# PowerControl.net
KiCad netlist of a schematic drawn in Altium Designer
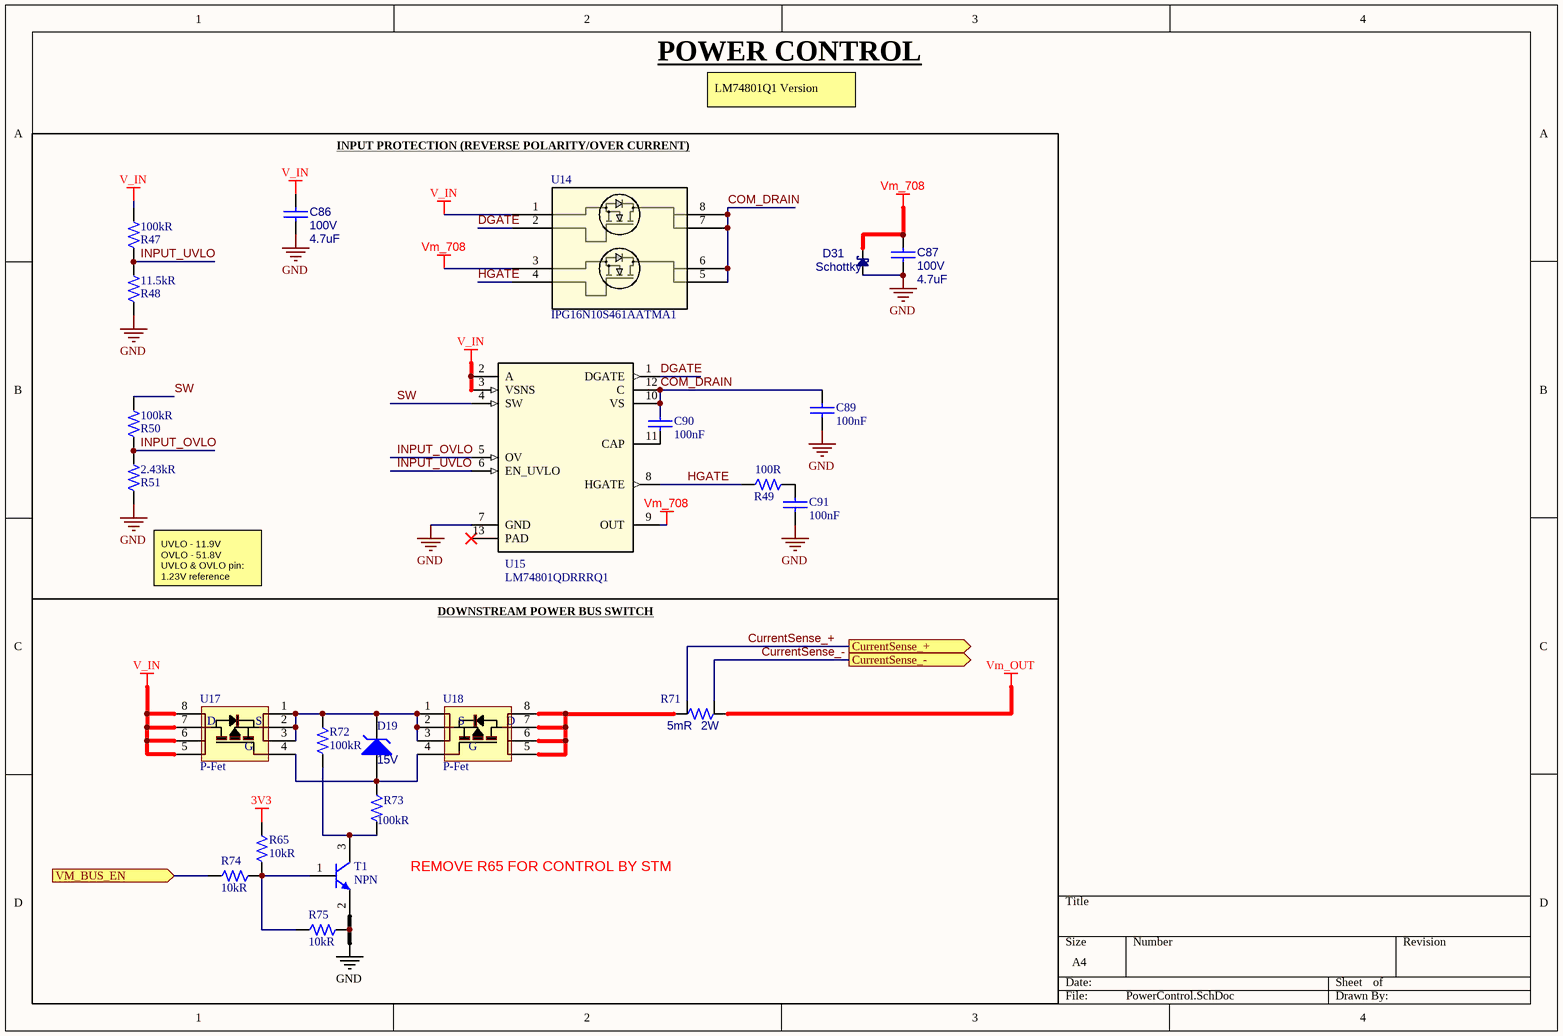
[diagram p0: PowerControl.SchDoc]

(export (version "E")
  (design (tool "Eeschema 10.0.6"))
  (components
    (comp (ref "C86")
      (value "4.7uF")
      (footprint "CAP1210")
      (description "Cap Ceramic 4.7uF 100V X7S 10% Pad SMD 1210 Soft Termination 125°C Automotive T/R")
      (fields
        (field (name "TOLERANCE") "10%")
        (field (name "VOLTAGE") "100V")
        (field (name "Comment") "Capacitor")
      )
      (libsource (lib "BPL-ShematicLibrary") (part "Capacitor"))
    )
    (comp (ref "C87")
      (value "4.7uF")
      (footprint "CAP1210")
      (description "Cap Ceramic 4.7uF 100V X7S 10% Pad SMD 1210 Soft Termination 125°C Automotive T/R")
      (fields
        (field (name "TOLERANCE") "10%")
        (field (name "VOLTAGE") "100V")
        (field (name "Comment") "Capacitor")
      )
      (libsource (lib "BPL-ShematicLibrary") (part "Capacitor"))
    )
    (comp (ref "C89")
      (value "Capacitor")
      (footprint "CAP0402")
      (description "Cap Ceramic 0.1uF 35V X7R 20% SMD 0402 125°C Punched Paper T/R")
      (fields (field (name "CAPACITANCE") "100nF"))
      (libsource (lib "BPL-ShematicLibrary") (part "Capacitor"))
    )
    (comp (ref "C90")
      (value "Capacitor")
      (footprint "CAP0402")
      (description "Cap Ceramic 0.1uF 35V X7R 20% SMD 0402 125°C Punched Paper T/R")
      (fields (field (name "CAPACITANCE") "100nF"))
      (libsource (lib "BPL-ShematicLibrary") (part "Capacitor"))
    )
    (comp (ref "C91")
      (value "Capacitor")
      (footprint "CAP0402")
      (description "Cap Ceramic 0.1uF 35V X7R 20% SMD 0402 125°C Punched Paper T/R")
      (fields (field (name "CAPACITANCE") "100nF"))
      (libsource (lib "BPL-ShematicLibrary") (part "Capacitor"))
    )
    (comp (ref "D19")
      (value "Zener")
      (footprint "SOD-323F")
      (fields (field (name "ZENER VOLTAGE") "15V"))
      (libsource (lib "BPL-ShematicLibrary") (part "Diode_Zener"))
    )
    (comp (ref "D31")
      (value "Schottky")
      (footprint "DO-214AC")
      (description "DIODE SCHOTTKY 5A 60V SMA")
      (libsource (lib "BPL-ShematicLibrary") (part "Diode_Shottky_2"))
    )
    (comp (ref "R47")
      (value "Resistor")
      (footprint "RES0402")
      (description "Res Thick Film 0402 100K Ohm 1% 0.063W(1/16W) ±100ppm/C Sulfur Resistant Pad SMD Automotive T/R")
      (fields
        (field (name "MANUFACTURER") "Yageo")
        (field (name "MANUFACTURER PART NUMBER") "AF0402FR-07100KL")
        (field (name "RESISTANCE") "100kR")
      )
      (libsource (lib "BPL-ShematicLibrary") (part "Resistor"))
    )
    (comp (ref "R48")
      (value "Resistor")
      (footprint "RES0402")
      (description "Res Thick Film 0402 11.5K Ohm 1% 0.063W(1/16W) ±100ppm/C Pad SMD Automotive T/R")
      (fields
        (field (name "MANUFACTURER") "Yageo")
        (field (name "MANUFACTURER PART NUMBER") "AC0402FR-0711K5L")
        (field (name "RESISTANCE") "11.5kR")
      )
      (libsource (lib "BPL-ShematicLibrary") (part "Resistor"))
    )
    (comp (ref "R49")
      (value "Resistor")
      (footprint "RES0402")
      (description "Res Thick Film 0402 100 Ohm 0.5% 0.063W ±50ppm/°C Molded SMD Punched Carrier T/R")
      (fields
        (field (name "MANUFACTURER") "Panasonic")
        (field (name "MANUFACTURER PART NUMBER") "ERJ-2RHD1000X")
        (field (name "RESISTANCE") "100R")
      )
      (libsource (lib "BPL-ShematicLibrary") (part "Resistor"))
    )
    (comp (ref "R50")
      (value "Resistor")
      (footprint "RES0402")
      (description "Res Thick Film 0402 100K Ohm 1% 0.063W(1/16W) ±100ppm/C Sulfur Resistant Pad SMD Automotive T/R")
      (fields
        (field (name "MANUFACTURER") "Yageo")
        (field (name "MANUFACTURER PART NUMBER") "AF0402FR-07100KL")
        (field (name "RESISTANCE") "100kR")
      )
      (libsource (lib "BPL-ShematicLibrary") (part "Resistor"))
    )
    (comp (ref "R51")
      (value "Resistor")
      (footprint "RES0402")
      (description "Res Anti Sulfur 0402 2.43K Ohm 1/16W 1% SMD")
      (fields
        (field (name "MANUFACTURER") "Rohm")
        (field (name "MANUFACTURER PART NUMBER") "TRR01MZPF2431")
        (field (name "RESISTANCE") "2.43kR")
      )
      (libsource (lib "BPL-ShematicLibrary") (part "Resistor"))
    )
    (comp (ref "R65")
      (value "Resistor")
      (footprint "RES0402")
      (fields (field (name "RESISTANCE") "10kR") (field (name "TOLERANCE") "1%"))
      (libsource (lib "BPL-ShematicLibrary") (part "Resistor"))
    )
    (comp (ref "R71")
      (value "Resistor_Kelvin")
      (footprint "RES2512 - KELVIN")
      (description "RES 0.005 OHM 1% 2W 2512")
      (fields
        (field (name "RESISTANCE") "5mR")
        (field (name "TOLERANCE") "1%")
        (field (name "POWER RATING") "2W")
      )
      (libsource (lib "BPL-ShematicLibrary") (part "Resistor_Kelvin"))
    )
    (comp (ref "R72")
      (value "Resistor")
      (footprint "RES0402")
      (fields (field (name "TOLERANCE") "1%") (field (name "RESISTANCE") "100kR"))
      (libsource (lib "BPL-ShematicLibrary") (part "Resistor"))
    )
    (comp (ref "R73")
      (value "Resistor")
      (footprint "RES0402")
      (fields (field (name "TOLERANCE") "1%") (field (name "RESISTANCE") "100kR"))
      (libsource (lib "BPL-ShematicLibrary") (part "Resistor"))
    )
    (comp (ref "R74")
      (value "Resistor")
      (footprint "RES0402")
      (fields (field (name "RESISTANCE") "10kR") (field (name "TOLERANCE") "1%"))
      (libsource (lib "BPL-ShematicLibrary") (part "Resistor"))
    )
    (comp (ref "R75")
      (value "Resistor")
      (footprint "RES0402")
      (fields (field (name "RESISTANCE") "10kR") (field (name "TOLERANCE") "1%"))
      (libsource (lib "BPL-ShematicLibrary") (part "Resistor"))
    )
    (comp (ref "T1")
      (value "NPN")
      (footprint "DFN2020D-3")
      (description "Trans GP BJT NPN 80V 3-Pin SOT-1061D T/R")
      (libsource (lib "BPL-ShematicLibrary") (part "NPN Transistor"))
    )
    (comp (ref "U14")
      (value "IPG16N10S461AATMA1")
      (footprint "PG-TDSON-8-4_INF")
      (description "MOSFET MOSFET_(75V 120V(")
      (fields (field (name "COPYRIGHT") "Copyright (C) 2021 Ultra Librarian. All rights reserved."))
      (libsource (lib "RS2-708_alt") (part "IPG16N10S461AATMA1"))
    )
    (comp (ref "U15")
      (value "LM74801QDRRRQ1")
      (footprint "DRR0012E")
      (description "No Description Available")
      (fields
        (field (name "MANUFACTURER_PART_NUMBER") "LM74800QDRRRQ1")
        (field (name "COPYRIGHT") "Copyright (C) 2021 Ultra Librarian. All rights reserved.")
      )
      (libsource (lib "RS2-708_alt") (part "LM74800QDRRRQ1"))
    )
    (comp (ref "U17")
      (value "P-Fet")
      (footprint "SO-8_PowerPAK")
      (description "Trans MOSFET P-CH 80V 10.2A 8-Pin PowerPAK SO T/R")
      (fields (field (name "VOLTAGE") "80V"))
      (libsource (lib "BPL-ShematicLibrary") (part "MOSFET - P - Single"))
    )
    (comp (ref "U18")
      (value "P-Fet")
      (footprint "SO-8_PowerPAK")
      (description "Trans MOSFET P-CH 80V 10.2A 8-Pin PowerPAK SO T/R")
      (fields (field (name "VOLTAGE") "80V"))
      (libsource (lib "") (part "MOSFET - P - Single_1"))
    )
  )
  (nets
    (net (code "1") (name "/COM_DRAIN") (class "Default")
      (node (ref "C89") (pin "1") (pinfunction "1_1") (pintype "passive"))
      (node (ref "C90") (pin "1") (pinfunction "1_1") (pintype "passive"))
      (node (ref "U14") (pin "5") (pinfunction "5_5") (pintype "passive"))
      (node (ref "U14") (pin "6") (pinfunction "6_6") (pintype "passive"))
      (node (ref "U14") (pin "7") (pinfunction "7_7") (pintype "passive"))
      (node (ref "U14") (pin "8") (pinfunction "8_8") (pintype "passive"))
      (node (ref "U15") (pin "10") (pinfunction "VS_10") (pintype "power_in"))
      (node (ref "U15") (pin "12") (pinfunction "C_12") (pintype "passive"))
    )
    (net (code "2") (name "/CurrentSense_+") (class "Default")
      (node (ref "R71") (pin "3") (pinfunction "3_3") (pintype "passive"))
    )
    (net (code "3") (name "/CurrentSense_-") (class "Default")
      (node (ref "R71") (pin "4") (pinfunction "4_4") (pintype "passive"))
    )
    (net (code "4") (name "/DGATE") (class "Default")
      (node (ref "U14") (pin "2") (pinfunction "2_2") (pintype "passive"))
      (node (ref "U15") (pin "1") (pinfunction "DGATE_1") (pintype "output"))
    )
    (net (code "5") (name "/HGATE") (class "Default")
      (node (ref "R49") (pin "2") (pinfunction "2_2") (pintype "passive"))
      (node (ref "U14") (pin "4") (pinfunction "4_4") (pintype "passive"))
      (node (ref "U15") (pin "8") (pinfunction "HGATE_8") (pintype "output"))
    )
    (net (code "6") (name "/INPUT_OVLO") (class "Default")
      (node (ref "R50") (pin "1") (pinfunction "1_1") (pintype "passive"))
      (node (ref "R51") (pin "2") (pinfunction "2_2") (pintype "passive"))
      (node (ref "U15") (pin "5") (pinfunction "OV_5") (pintype "input"))
    )
    (net (code "7") (name "/INPUT_UVLO") (class "Default")
      (node (ref "R47") (pin "1") (pinfunction "1_1") (pintype "passive"))
      (node (ref "R48") (pin "2") (pinfunction "2_2") (pintype "passive"))
      (node (ref "U15") (pin "6") (pinfunction "EN_UVLO_6") (pintype "input"))
    )
    (net (code "8") (name "/SW") (class "Default")
      (node (ref "R50") (pin "2") (pinfunction "2_2") (pintype "passive"))
      (node (ref "U15") (pin "4") (pinfunction "SW_4") (pintype "input"))
    )
    (net (code "9") (name "/VM_BUS_EN") (class "Default")
      (node (ref "R74") (pin "1") (pinfunction "1_1") (pintype "passive"))
    )
    (net (code "10") (name "3V3") (class "Default")
      (node (ref "R65") (pin "2") (pinfunction "2_2") (pintype "passive"))
    )
    (net (code "11") (name "GND") (class "Default")
      (node (ref "C86") (pin "2") (pinfunction "2_2") (pintype "passive"))
      (node (ref "C87") (pin "2") (pinfunction "2_2") (pintype "passive"))
      (node (ref "C89") (pin "2") (pinfunction "2_2") (pintype "passive"))
      (node (ref "C91") (pin "2") (pinfunction "2_2") (pintype "passive"))
      (node (ref "D31") (pin "2") (pinfunction "2_2") (pintype "passive"))
      (node (ref "R48") (pin "1") (pinfunction "1_1") (pintype "passive"))
      (node (ref "R51") (pin "1") (pinfunction "1_1") (pintype "passive"))
      (node (ref "R75") (pin "2") (pinfunction "2_2") (pintype "passive"))
      (node (ref "T1") (pin "2") (pinfunction "E_2") (pintype "passive"))
      (node (ref "U15") (pin "7") (pinfunction "GND_7") (pintype "power_in"))
    )
    (net (code "12") (name "Net-(C91-Pad1)") (class "Default")
      (node (ref "C91") (pin "1") (pinfunction "1_1") (pintype "passive"))
      (node (ref "R49") (pin "1") (pinfunction "1_1") (pintype "passive"))
    )
    (net (code "13") (name "Net-(D19-Pad2)") (class "Default")
      (node (ref "D19") (pin "2") (pinfunction "2_2") (pintype "passive"))
      (node (ref "R73") (pin "1") (pinfunction "1_1") (pintype "passive"))
      (node (ref "U17") (pin "4") (pinfunction "4_4") (pintype "passive"))
      (node (ref "U18") (pin "4") (pinfunction "4_4") (pintype "passive"))
    )
    (net (code "14") (name "Net-(R71-Pad1)") (class "Default")
      (node (ref "R71") (pin "1") (pinfunction "1_1") (pintype "passive"))
      (node (ref "U18") (pin "5") (pinfunction "5_5") (pintype "passive"))
      (node (ref "U18") (pin "6") (pinfunction "6_6") (pintype "passive"))
      (node (ref "U18") (pin "7") (pinfunction "7_7") (pintype "passive"))
      (node (ref "U18") (pin "8") (pinfunction "8_8") (pintype "passive"))
    )
    (net (code "15") (name "Net-(T1-B)") (class "Default")
      (node (ref "R65") (pin "1") (pinfunction "1_1") (pintype "passive"))
      (node (ref "R74") (pin "2") (pinfunction "2_2") (pintype "passive"))
      (node (ref "R75") (pin "1") (pinfunction "1_1") (pintype "passive"))
      (node (ref "T1") (pin "1") (pinfunction "B_1") (pintype "passive"))
    )
    (net (code "16") (name "Net-(T1-C)") (class "Default")
      (node (ref "R72") (pin "2") (pinfunction "2_2") (pintype "passive"))
      (node (ref "R73") (pin "2") (pinfunction "2_2") (pintype "passive"))
      (node (ref "T1") (pin "3") (pinfunction "C_3") (pintype "passive"))
    )
    (net (code "17") (name "Net-(U15-CAP)") (class "Default")
      (node (ref "C90") (pin "2") (pinfunction "2_2") (pintype "passive"))
      (node (ref "U15") (pin "11") (pinfunction "CAP_11") (pintype "passive"))
    )
    (net (code "18") (name "Net-(U17-D)") (class "Default")
      (node (ref "D19") (pin "1") (pinfunction "1_1") (pintype "passive"))
      (node (ref "R72") (pin "1") (pinfunction "1_1") (pintype "passive"))
      (node (ref "U17") (pin "1") (pinfunction "G_1") (pintype "passive"))
      (node (ref "U17") (pin "2") (pinfunction "S_2") (pintype "passive"))
      (node (ref "U17") (pin "3") (pinfunction "D_3") (pintype "passive"))
      (node (ref "U18") (pin "1") (pinfunction "G_1") (pintype "passive"))
      (node (ref "U18") (pin "2") (pinfunction "S_2") (pintype "passive"))
      (node (ref "U18") (pin "3") (pinfunction "D_3") (pintype "passive"))
    )
    (net (code "19") (name "V_IN") (class "Default")
      (node (ref "C86") (pin "1") (pinfunction "1_1") (pintype "passive"))
      (node (ref "R47") (pin "2") (pinfunction "2_2") (pintype "passive"))
      (node (ref "U14") (pin "1") (pinfunction "1_1") (pintype "passive"))
      (node (ref "U15") (pin "2") (pinfunction "A_2") (pintype "passive"))
      (node (ref "U15") (pin "3") (pinfunction "VSNS_3") (pintype "input"))
      (node (ref "U17") (pin "5") (pinfunction "5_5") (pintype "passive"))
      (node (ref "U17") (pin "6") (pinfunction "6_6") (pintype "passive"))
      (node (ref "U17") (pin "7") (pinfunction "7_7") (pintype "passive"))
      (node (ref "U17") (pin "8") (pinfunction "8_8") (pintype "passive"))
    )
    (net (code "20") (name "Vm_708") (class "Default")
      (node (ref "C87") (pin "1") (pinfunction "1_1") (pintype "passive"))
      (node (ref "D31") (pin "1") (pinfunction "1_1") (pintype "passive"))
      (node (ref "U14") (pin "3") (pinfunction "3_3") (pintype "passive"))
      (node (ref "U15") (pin "9") (pinfunction "OUT_9") (pintype "passive"))
    )
    (net (code "21") (name "Vm_OUT") (class "Default")
      (node (ref "R71") (pin "2") (pinfunction "2_2") (pintype "passive"))
    )
    (net (code "22") (name "unconnected-(U15-PAD-Pad13)") (class "Default")
      (node (ref "U15") (pin "13") (pinfunction "PAD_13") (pintype "passive+no_connect"))
    )
  )
)
